# pentabug_1layer.net
KiCad netlist of a schematic drawn in EAGLE
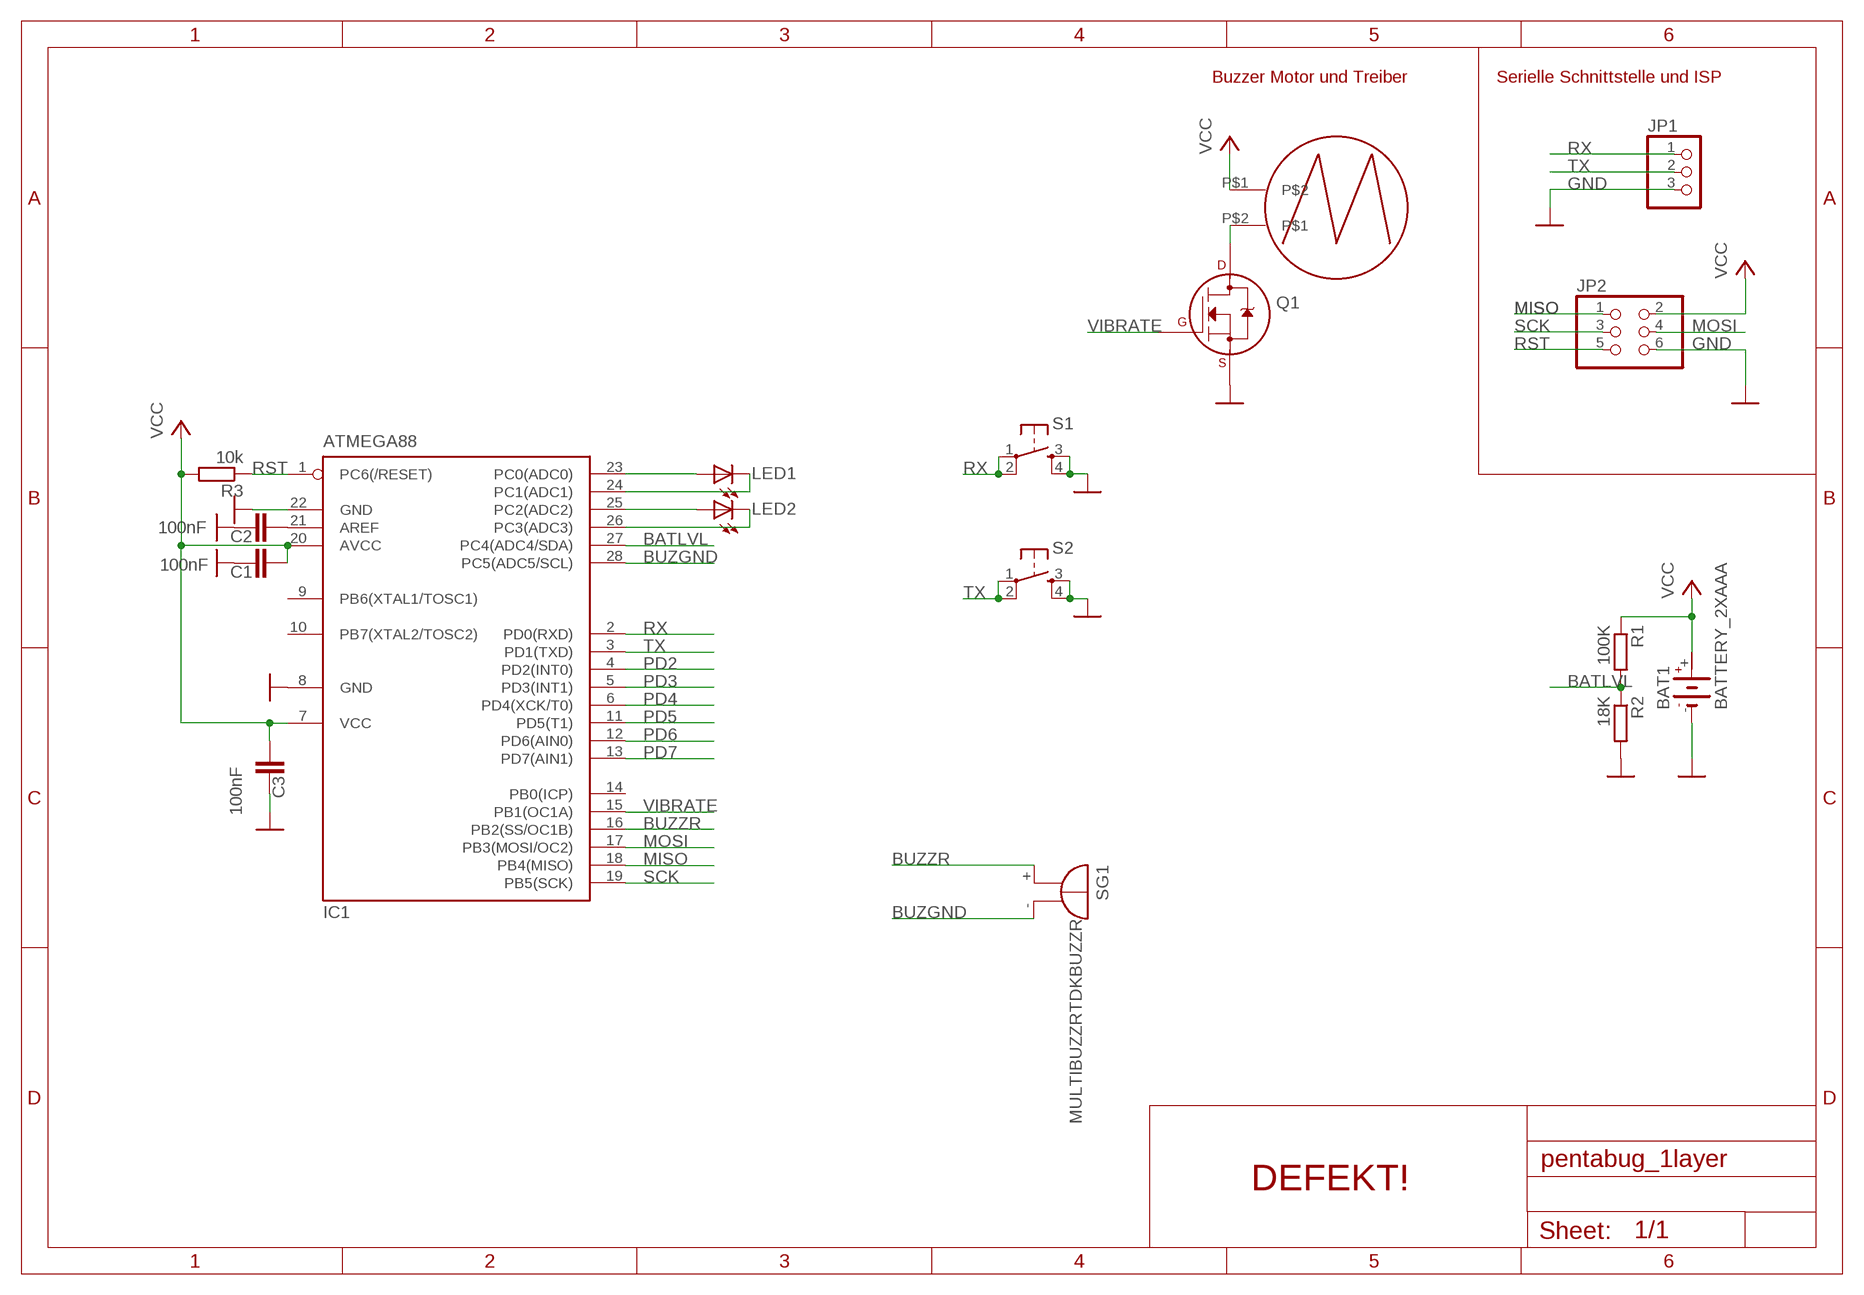
[diagram p0: schematic, sheet 1]

(export (version "E")
  (design (tool "Eeschema 10.0.6"))
  (components
    (comp (ref "BAT1")
      (value "BATTERY_2XAAA")
      (footprint "eagle-import:BATTERY_2XAAA")
      (libsource (lib "eagle-import") (part "BATTERY_2XAAA"))
    )
    (comp (ref "C1")
      (value "100nF")
      (footprint "eagle-import:C025-024X044")
      (libsource (lib "eagle-import") (part "C-EU025-024X044"))
    )
    (comp (ref "C2")
      (value "100nF")
      (footprint "eagle-import:C025-024X044")
      (libsource (lib "eagle-import") (part "C-EU025-024X044"))
    )
    (comp (ref "C3")
      (value "100nF")
      (footprint "eagle-import:C025-024X044")
      (libsource (lib "eagle-import") (part "C-EU025-024X044"))
    )
    (comp (ref "IC1")
      (value "ATMEGA88")
      (footprint "eagle-import:DIL28-3")
      (libsource (lib "eagle-import") (part "MEGA8-P"))
    )
    (comp (ref "JP1")
      (value "PINHD-1X3")
      (footprint "eagle-import:1X03")
      (libsource (lib "eagle-import") (part "PINHD-1X3"))
    )
    (comp (ref "JP2")
      (value "PINHD-2X3")
      (footprint "eagle-import:2X03")
      (libsource (lib "eagle-import") (part "PINHD-2X3"))
    )
    (comp (ref "LED1")
      (value "LED5MM")
      (footprint "eagle-import:LED5MM")
      (libsource (lib "eagle-import") (part "LED5MM"))
    )
    (comp (ref "LED2")
      (value "LED5MM")
      (footprint "eagle-import:LED5MM")
      (libsource (lib "eagle-import") (part "LED5MM"))
    )
    (comp (ref "Q1")
      (value "2N7000_TO92")
      (footprint "eagle-import:TO-92")
      (libsource (lib "eagle-import") (part "2N700_TO920"))
    )
    (comp (ref "R1")
      (value "100K")
      (footprint "eagle-import:0207_10")
      (libsource (lib "eagle-import") (part "R-EU_0207/10"))
    )
    (comp (ref "R2")
      (value "18K")
      (footprint "eagle-import:0207_10")
      (libsource (lib "eagle-import") (part "R-EU_0207/10"))
    )
    (comp (ref "R3")
      (value "10k")
      (footprint "eagle-import:0207_10")
      (libsource (lib "eagle-import") (part "R-EU_0207/10"))
    )
    (comp (ref "S1")
      (value "TAC_SWITCHPTH")
      (footprint "eagle-import:TACTILE-PTH")
      (libsource (lib "eagle-import") (part "TAC_SWITCHPTH"))
    )
    (comp (ref "S2")
      (value "TAC_SWITCHPTH")
      (footprint "eagle-import:TACTILE-PTH")
      (libsource (lib "eagle-import") (part "TAC_SWITCHPTH"))
    )
    (comp (ref "SG1")
      (value "MULTIBUZZRTDKBUZZR")
      (footprint "eagle-import:BUZZRTDK")
      (libsource (lib "eagle-import") (part "MULTIBUZZRTDKBUZZR"))
    )
    (comp (ref "U$1")
      (value "VIBRAMOTOR")
      (footprint "eagle-import:LA4-432")
      (libsource (lib "eagle-import") (part "VIBRAMOTOR"))
    )
  )
  (nets
    (net (code "1") (name "/BATLVL") (class "Default")
      (node (ref "IC1") (pin "27") (pinfunction "PC4(ADC4/SDA)_27") (pintype "bidirectional"))
      (node (ref "R1") (pin "2") (pinfunction "2_2") (pintype "passive"))
      (node (ref "R2") (pin "1") (pinfunction "1_1") (pintype "passive"))
    )
    (net (code "2") (name "/BUZGND") (class "Default")
      (node (ref "IC1") (pin "28") (pinfunction "PC5(ADC5/SCL)_28") (pintype "bidirectional"))
      (node (ref "SG1") (pin "-") (pinfunction "-_-") (pintype "passive"))
    )
    (net (code "3") (name "/BUZZR") (class "Default")
      (node (ref "IC1") (pin "16") (pinfunction "PB2(SS/OC1B)_16") (pintype "bidirectional"))
      (node (ref "SG1") (pin "+") (pinfunction "+_+") (pintype "passive"))
    )
    (net (code "4") (name "/MISO") (class "Default")
      (node (ref "IC1") (pin "18") (pinfunction "PB4(MISO)_18") (pintype "bidirectional"))
      (node (ref "JP2") (pin "1") (pinfunction "1_1") (pintype "passive"))
    )
    (net (code "5") (name "/MOSI") (class "Default")
      (node (ref "IC1") (pin "17") (pinfunction "PB3(MOSI/OC2)_17") (pintype "bidirectional"))
      (node (ref "JP2") (pin "4") (pinfunction "4_4") (pintype "passive"))
    )
    (net (code "6") (name "/PD2") (class "Default")
      (node (ref "IC1") (pin "4") (pinfunction "PD2(INT0)_4") (pintype "bidirectional"))
    )
    (net (code "7") (name "/PD3") (class "Default")
      (node (ref "IC1") (pin "5") (pinfunction "PD3(INT1)_5") (pintype "bidirectional"))
    )
    (net (code "8") (name "/PD4") (class "Default")
      (node (ref "IC1") (pin "6") (pinfunction "PD4(XCK/T0)_6") (pintype "bidirectional"))
    )
    (net (code "9") (name "/PD5") (class "Default")
      (node (ref "IC1") (pin "11") (pinfunction "PD5(T1)_11") (pintype "bidirectional"))
    )
    (net (code "10") (name "/PD6") (class "Default")
      (node (ref "IC1") (pin "12") (pinfunction "PD6(AIN0)_12") (pintype "bidirectional"))
    )
    (net (code "11") (name "/PD7") (class "Default")
      (node (ref "IC1") (pin "13") (pinfunction "PD7(AIN1)_13") (pintype "bidirectional"))
    )
    (net (code "12") (name "/RST") (class "Default")
      (node (ref "IC1") (pin "1") (pinfunction "PC6(/RESET)_1") (pintype "bidirectional"))
      (node (ref "JP2") (pin "5") (pinfunction "5_5") (pintype "passive"))
      (node (ref "R3") (pin "1") (pinfunction "1_1") (pintype "passive"))
    )
    (net (code "13") (name "/RX") (class "Default")
      (node (ref "IC1") (pin "2") (pinfunction "PD0(RXD)_2") (pintype "bidirectional"))
      (node (ref "JP1") (pin "1") (pinfunction "1_1") (pintype "passive"))
      (node (ref "S1") (pin "1") (pinfunction "1_1") (pintype "passive"))
      (node (ref "S1") (pin "2") (pinfunction "2_2") (pintype "passive"))
    )
    (net (code "14") (name "/SCK") (class "Default")
      (node (ref "IC1") (pin "19") (pinfunction "PB5(SCK)_19") (pintype "bidirectional"))
      (node (ref "JP2") (pin "3") (pinfunction "3_3") (pintype "passive"))
    )
    (net (code "15") (name "/TX") (class "Default")
      (node (ref "IC1") (pin "3") (pinfunction "PD1(TXD)_3") (pintype "bidirectional"))
      (node (ref "JP1") (pin "2") (pinfunction "2_2") (pintype "passive"))
      (node (ref "S2") (pin "1") (pinfunction "1_1") (pintype "passive"))
      (node (ref "S2") (pin "2") (pinfunction "2_2") (pintype "passive"))
    )
    (net (code "16") (name "/VIBRATE") (class "Default")
      (node (ref "IC1") (pin "15") (pinfunction "PB1(OC1A)_15") (pintype "bidirectional"))
      (node (ref "Q1") (pin "2") (pinfunction "G_2") (pintype "tri_state"))
    )
    (net (code "17") (name "GND") (class "Default")
      (node (ref "BAT1") (pin "-") (pinfunction "-_-") (pintype "passive"))
      (node (ref "C1") (pin "1") (pinfunction "1_1") (pintype "passive"))
      (node (ref "C2") (pin "1") (pinfunction "1_1") (pintype "passive"))
      (node (ref "C3") (pin "1") (pinfunction "1_1") (pintype "passive"))
      (node (ref "IC1") (pin "22") (pinfunction "GND_22") (pintype "power_in"))
      (node (ref "IC1") (pin "8") (pinfunction "GND_8") (pintype "power_in"))
      (node (ref "JP1") (pin "3") (pinfunction "3_3") (pintype "passive"))
      (node (ref "JP2") (pin "6") (pinfunction "6_6") (pintype "passive"))
      (node (ref "Q1") (pin "1") (pinfunction "S_1") (pintype "bidirectional"))
      (node (ref "R2") (pin "2") (pinfunction "2_2") (pintype "passive"))
      (node (ref "S1") (pin "3") (pinfunction "3_3") (pintype "passive"))
      (node (ref "S1") (pin "4") (pinfunction "4_4") (pintype "passive"))
      (node (ref "S2") (pin "3") (pinfunction "3_3") (pintype "passive"))
      (node (ref "S2") (pin "4") (pinfunction "4_4") (pintype "passive"))
    )
    (net (code "18") (name "Net-(IC1-AREF)") (class "Default")
      (node (ref "C2") (pin "2") (pinfunction "2_2") (pintype "passive"))
      (node (ref "IC1") (pin "21") (pinfunction "AREF_21") (pintype "passive"))
    )
    (net (code "19") (name "Net-(IC1-PC0(ADC0))") (class "Default")
      (node (ref "IC1") (pin "23") (pinfunction "PC0(ADC0)_23") (pintype "bidirectional"))
      (node (ref "LED1") (pin "A") (pinfunction "A_A") (pintype "passive"))
    )
    (net (code "20") (name "Net-(IC1-PC1(ADC1))") (class "Default")
      (node (ref "IC1") (pin "24") (pinfunction "PC1(ADC1)_24") (pintype "bidirectional"))
      (node (ref "LED1") (pin "K") (pinfunction "C_K") (pintype "passive"))
    )
    (net (code "21") (name "Net-(IC1-PC2(ADC2))") (class "Default")
      (node (ref "IC1") (pin "25") (pinfunction "PC2(ADC2)_25") (pintype "bidirectional"))
      (node (ref "LED2") (pin "A") (pinfunction "A_A") (pintype "passive"))
    )
    (net (code "22") (name "Net-(IC1-PC3(ADC3))") (class "Default")
      (node (ref "IC1") (pin "26") (pinfunction "PC3(ADC3)_26") (pintype "bidirectional"))
      (node (ref "LED2") (pin "K") (pinfunction "C_K") (pintype "passive"))
    )
    (net (code "23") (name "Net-(Q1-D)") (class "Default")
      (node (ref "Q1") (pin "3") (pinfunction "D_3") (pintype "bidirectional"))
      (node (ref "U$1") (pin "P$2") (pinfunction "P$1_P$2") (pintype "power_in"))
    )
    (net (code "24") (name "VCC") (class "Default")
      (node (ref "BAT1") (pin "+") (pinfunction "+_+") (pintype "passive"))
      (node (ref "C1") (pin "2") (pinfunction "2_2") (pintype "passive"))
      (node (ref "C3") (pin "2") (pinfunction "2_2") (pintype "passive"))
      (node (ref "IC1") (pin "20") (pinfunction "AVCC_20") (pintype "power_in"))
      (node (ref "IC1") (pin "7") (pinfunction "VCC_7") (pintype "power_in"))
      (node (ref "JP2") (pin "2") (pinfunction "2_2") (pintype "passive"))
      (node (ref "R1") (pin "1") (pinfunction "1_1") (pintype "passive"))
      (node (ref "R3") (pin "2") (pinfunction "2_2") (pintype "passive"))
      (node (ref "U$1") (pin "P$1") (pinfunction "P$2_P$1") (pintype "power_in"))
    )
    (net (code "25") (name "unconnected-(IC1-PB0(ICP)-Pad14)") (class "Default")
      (node (ref "IC1") (pin "14") (pinfunction "PB0(ICP)_14") (pintype "bidirectional"))
    )
    (net (code "26") (name "unconnected-(IC1-PB6(XTAL1{slash}TOSC1)-Pad9)") (class "Default")
      (node (ref "IC1") (pin "9") (pinfunction "PB6(XTAL1/TOSC1)_9") (pintype "bidirectional"))
    )
    (net (code "27") (name "unconnected-(IC1-PB7(XTAL2{slash}TOSC2)-Pad10)") (class "Default")
      (node (ref "IC1") (pin "10") (pinfunction "PB7(XTAL2/TOSC2)_10") (pintype "bidirectional"))
    )
  )
)
